# MRCS-8xDPDT-Relay.net
KiCad netlist of a schematic drawn in EAGLE
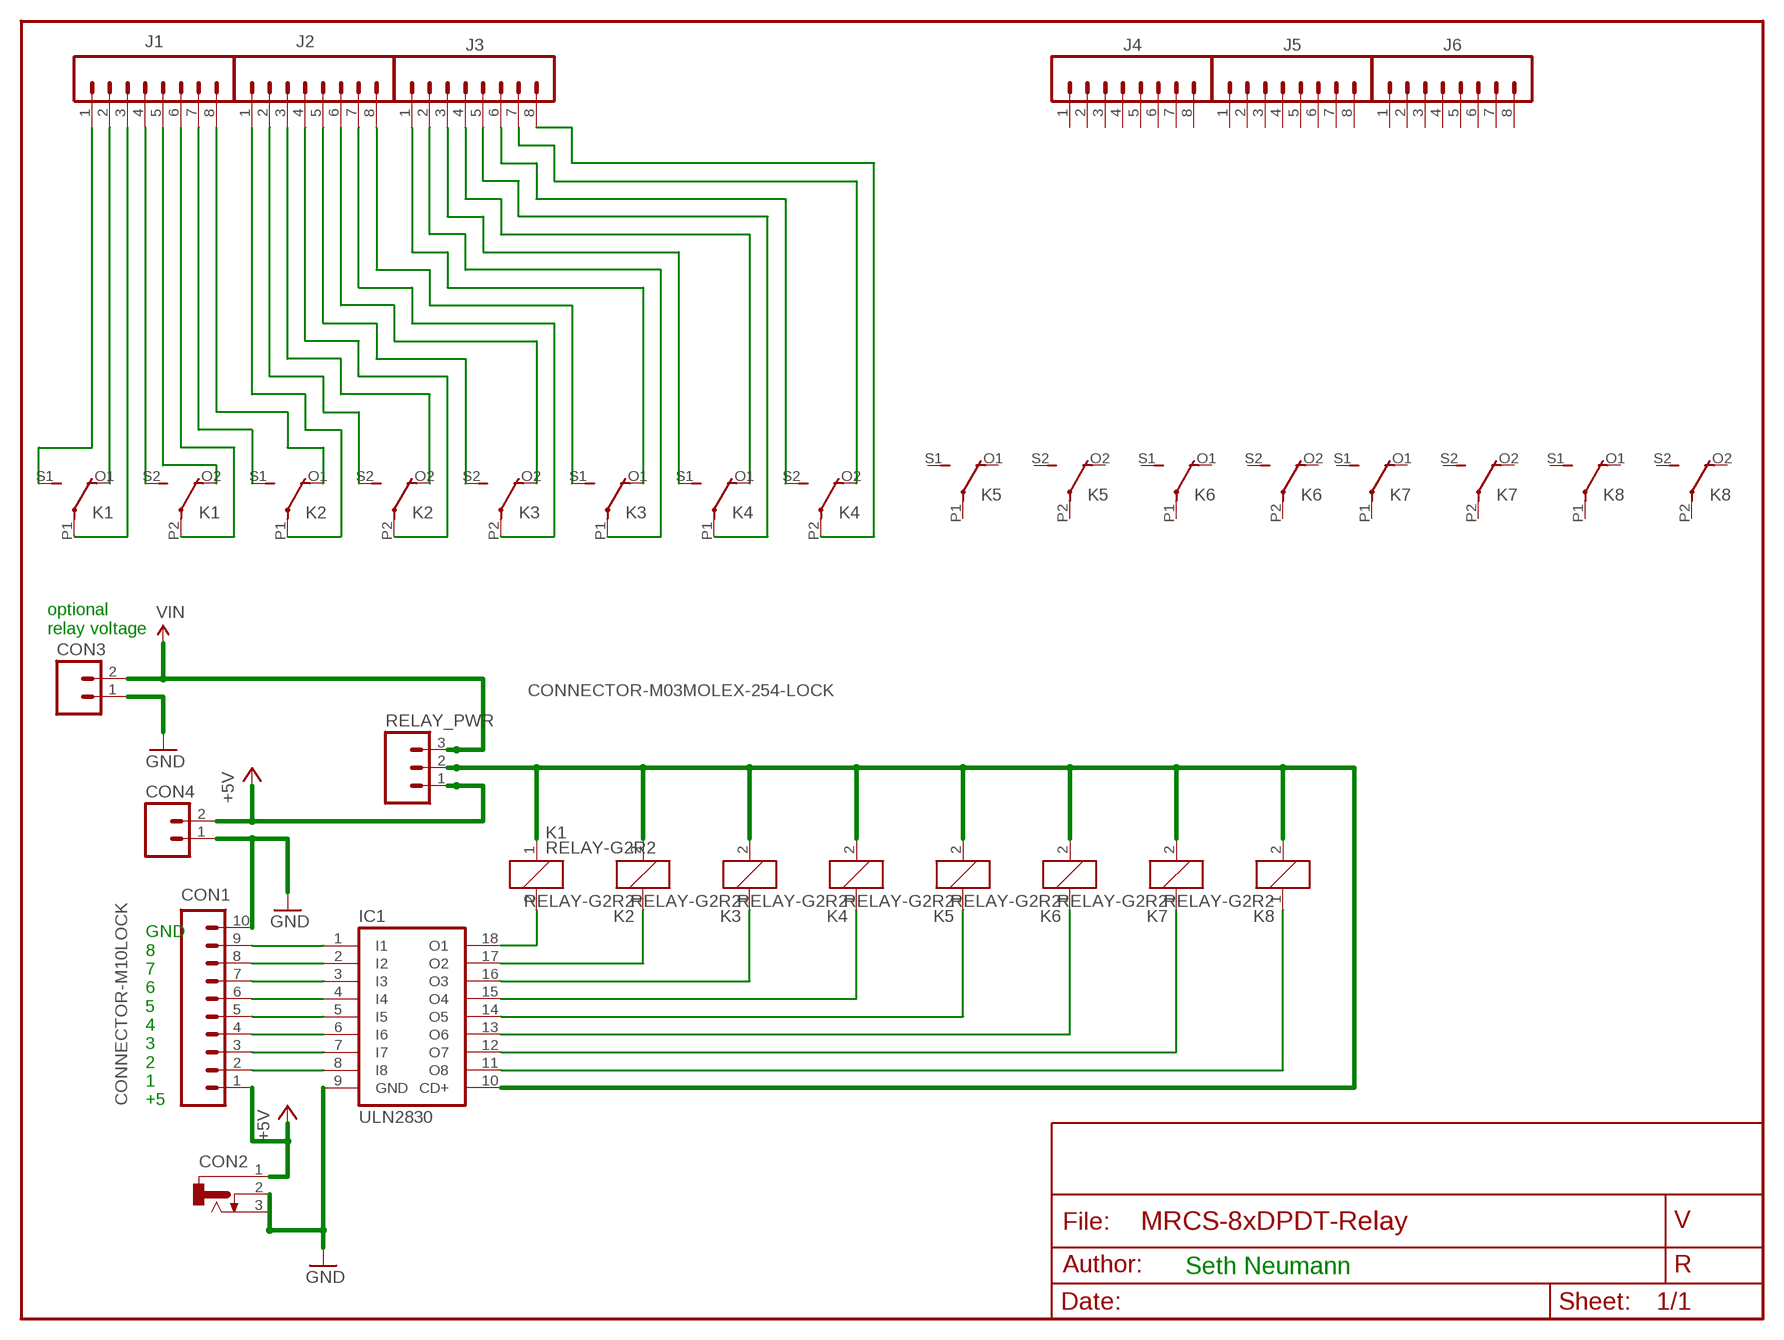
[diagram p0: schematic, sheet 1]

(export (version "E")
  (design (tool "Eeschema 10.0.6"))
  (components
    (comp (ref "CON1")
      (value "CONNECTOR-M10LOCK")
      (footprint "eagle-import:1X10_LOCK")
      (libsource (lib "eagle-import") (part "CONNECTOR-M10LOCK"))
    )
    (comp (ref "CON2")
      (value "CONNECTOR-DC-POWER-RA")
      (footprint "eagle-import:DCJ0202")
      (libsource (lib "eagle-import") (part "CONNECTOR-DC-POWER-RA"))
    )
    (comp (ref "CON3")
      (value "CONNECTOR-M023.5MM-LOCK")
      (footprint "eagle-import:SCREWTERMINAL-3.5MM-2_LOCK")
      (libsource (lib "eagle-import") (part "CONNECTOR-M023.5MM-LOCK"))
    )
    (comp (ref "CON4")
      (value "CONNECTOR-M023.5MM-LOCK")
      (footprint "eagle-import:SCREWTERMINAL-3.5MM-2_LOCK")
      (libsource (lib "eagle-import") (part "CONNECTOR-M023.5MM-LOCK"))
    )
    (comp (ref "IC1")
      (value "ULN2830")
      (footprint "eagle-import:DIL18")
      (libsource (lib "eagle-import") (part "ULN2803A"))
    )
    (comp (ref "J1")
      (value "CONNECTOR-M08LOCK")
      (footprint "eagle-import:1X08_LOCK")
      (libsource (lib "eagle-import") (part "CONNECTOR-M08LOCK"))
    )
    (comp (ref "J2")
      (value "CONNECTOR-M08LOCK")
      (footprint "eagle-import:1X08_LOCK")
      (libsource (lib "eagle-import") (part "CONNECTOR-M08LOCK"))
    )
    (comp (ref "J3")
      (value "CONNECTOR-M08LOCK")
      (footprint "eagle-import:1X08_LOCK")
      (libsource (lib "eagle-import") (part "CONNECTOR-M08LOCK"))
    )
    (comp (ref "J4")
      (value "CONNECTOR-M08LOCK")
      (footprint "eagle-import:1X08_LOCK")
      (libsource (lib "eagle-import") (part "CONNECTOR-M08LOCK"))
    )
    (comp (ref "J5")
      (value "CONNECTOR-M08LOCK")
      (footprint "eagle-import:1X08_LOCK")
      (libsource (lib "eagle-import") (part "CONNECTOR-M08LOCK"))
    )
    (comp (ref "J6")
      (value "CONNECTOR-M08LOCK")
      (footprint "eagle-import:1X08_LOCK")
      (libsource (lib "eagle-import") (part "CONNECTOR-M08LOCK"))
    )
    (comp (ref "K1")
      (value "RELAY-G2R2")
      (footprint "eagle-import:G2R2")
      (fields (field (name "MF") "OMRON COMPONENTS USA") (field (name "MPN") "G2R-2-DC6"))
      (libsource (lib "eagle-import") (part "RELAY-G2R2"))
    )
    (comp (ref "K2")
      (value "RELAY-G2R2")
      (footprint "eagle-import:G2R2")
      (fields (field (name "MF") "OMRON COMPONENTS USA") (field (name "MPN") "G2R-2-DC6"))
      (libsource (lib "eagle-import") (part "RELAY-G2R2"))
    )
    (comp (ref "K3")
      (value "RELAY-G2R2")
      (footprint "eagle-import:G2R2")
      (fields (field (name "MF") "OMRON COMPONENTS USA") (field (name "MPN") "G2R-2-DC6"))
      (libsource (lib "eagle-import") (part "RELAY-G2R2"))
    )
    (comp (ref "K4")
      (value "RELAY-G2R2")
      (footprint "eagle-import:G2R2")
      (fields (field (name "MF") "OMRON COMPONENTS USA") (field (name "MPN") "G2R-2-DC6"))
      (libsource (lib "eagle-import") (part "RELAY-G2R2"))
    )
    (comp (ref "K5")
      (value "RELAY-G2R2")
      (footprint "eagle-import:G2R2")
      (fields (field (name "MF") "OMRON COMPONENTS USA") (field (name "MPN") "G2R-2-DC6"))
      (libsource (lib "eagle-import") (part "RELAY-G2R2"))
    )
    (comp (ref "K6")
      (value "RELAY-G2R2")
      (footprint "eagle-import:G2R2")
      (fields (field (name "MF") "OMRON COMPONENTS USA") (field (name "MPN") "G2R-2-DC6"))
      (libsource (lib "eagle-import") (part "RELAY-G2R2"))
    )
    (comp (ref "K7")
      (value "RELAY-G2R2")
      (footprint "eagle-import:G2R2")
      (fields (field (name "MF") "OMRON COMPONENTS USA") (field (name "MPN") "G2R-2-DC6"))
      (libsource (lib "eagle-import") (part "RELAY-G2R2"))
    )
    (comp (ref "K8")
      (value "RELAY-G2R2")
      (footprint "eagle-import:G2R2")
      (fields (field (name "MF") "OMRON COMPONENTS USA") (field (name "MPN") "G2R-2-DC6"))
      (libsource (lib "eagle-import") (part "RELAY-G2R2"))
    )
    (comp (ref "RELAY_PWR")
      (value "CONNECTOR-M03MOLEX-254-LOCK")
      (footprint "eagle-import:MOLEX-1X3_LOCK")
      (libsource (lib "eagle-import") (part "CONNECTOR-M03MOLEX-254-LOCK"))
    )
  )
  (nets
    (net (code "1") (name "+5V") (class "Default")
      (node (ref "CON1") (pin "1") (pinfunction "1_1") (pintype "passive"))
      (node (ref "CON2") (pin "1") (pinfunction "1_1") (pintype "passive"))
      (node (ref "CON4") (pin "2") (pinfunction "B_2") (pintype "passive"))
      (node (ref "RELAY_PWR") (pin "1") (pinfunction "1_1") (pintype "passive"))
    )
    (net (code "2") (name "GND") (class "Default")
      (node (ref "CON1") (pin "10") (pinfunction "10_10") (pintype "passive"))
      (node (ref "CON2") (pin "2") (pinfunction "2_2") (pintype "passive"))
      (node (ref "CON2") (pin "3") (pinfunction "3_3") (pintype "passive"))
      (node (ref "CON3") (pin "1") (pinfunction "A_1") (pintype "passive"))
      (node (ref "CON4") (pin "1") (pinfunction "A_1") (pintype "passive"))
      (node (ref "IC1") (pin "9") (pinfunction "GND_9") (pintype "power_in"))
    )
    (net (code "3") (name "Net-(IC1-CD+)") (class "Default")
      (node (ref "IC1") (pin "10") (pinfunction "CD+_10") (pintype "passive"))
      (node (ref "K1") (pin "1") (pinfunction "1_1") (pintype "passive"))
      (node (ref "K2") (pin "2") (pinfunction "2_2") (pintype "passive"))
      (node (ref "K3") (pin "2") (pinfunction "2_2") (pintype "passive"))
      (node (ref "K4") (pin "2") (pinfunction "2_2") (pintype "passive"))
      (node (ref "K5") (pin "2") (pinfunction "2_2") (pintype "passive"))
      (node (ref "K6") (pin "2") (pinfunction "2_2") (pintype "passive"))
      (node (ref "K7") (pin "2") (pinfunction "2_2") (pintype "passive"))
      (node (ref "K8") (pin "2") (pinfunction "2_2") (pintype "passive"))
      (node (ref "RELAY_PWR") (pin "2") (pinfunction "2_2") (pintype "passive"))
    )
    (net (code "4") (name "Net-(IC1-I1)") (class "Default")
      (node (ref "CON1") (pin "9") (pinfunction "9_9") (pintype "passive"))
      (node (ref "IC1") (pin "1") (pinfunction "I1_1") (pintype "input"))
    )
    (net (code "5") (name "Net-(IC1-I2)") (class "Default")
      (node (ref "CON1") (pin "8") (pinfunction "8_8") (pintype "passive"))
      (node (ref "IC1") (pin "2") (pinfunction "I2_2") (pintype "input"))
    )
    (net (code "6") (name "Net-(IC1-I3)") (class "Default")
      (node (ref "CON1") (pin "7") (pinfunction "7_7") (pintype "passive"))
      (node (ref "IC1") (pin "3") (pinfunction "I3_3") (pintype "input"))
    )
    (net (code "7") (name "Net-(IC1-I4)") (class "Default")
      (node (ref "CON1") (pin "6") (pinfunction "6_6") (pintype "passive"))
      (node (ref "IC1") (pin "4") (pinfunction "I4_4") (pintype "input"))
    )
    (net (code "8") (name "Net-(IC1-I5)") (class "Default")
      (node (ref "CON1") (pin "5") (pinfunction "5_5") (pintype "passive"))
      (node (ref "IC1") (pin "5") (pinfunction "I5_5") (pintype "input"))
    )
    (net (code "9") (name "Net-(IC1-I6)") (class "Default")
      (node (ref "CON1") (pin "4") (pinfunction "4_4") (pintype "passive"))
      (node (ref "IC1") (pin "6") (pinfunction "I6_6") (pintype "input"))
    )
    (net (code "10") (name "Net-(IC1-I7)") (class "Default")
      (node (ref "CON1") (pin "3") (pinfunction "3_3") (pintype "passive"))
      (node (ref "IC1") (pin "7") (pinfunction "I7_7") (pintype "input"))
    )
    (net (code "11") (name "Net-(IC1-I8)") (class "Default")
      (node (ref "CON1") (pin "2") (pinfunction "2_2") (pintype "passive"))
      (node (ref "IC1") (pin "8") (pinfunction "I8_8") (pintype "input"))
    )
    (net (code "12") (name "Net-(IC1-O1)") (class "Default")
      (node (ref "IC1") (pin "18") (pinfunction "O1_18") (pintype "open_collector"))
      (node (ref "K1") (pin "2") (pinfunction "2_2") (pintype "passive"))
    )
    (net (code "13") (name "Net-(IC1-O2)") (class "Default")
      (node (ref "IC1") (pin "17") (pinfunction "O2_17") (pintype "open_collector"))
      (node (ref "K2") (pin "1") (pinfunction "1_1") (pintype "passive"))
    )
    (net (code "14") (name "Net-(IC1-O3)") (class "Default")
      (node (ref "IC1") (pin "16") (pinfunction "O3_16") (pintype "open_collector"))
      (node (ref "K3") (pin "1") (pinfunction "1_1") (pintype "passive"))
    )
    (net (code "15") (name "Net-(IC1-O4)") (class "Default")
      (node (ref "IC1") (pin "15") (pinfunction "O4_15") (pintype "open_collector"))
      (node (ref "K4") (pin "1") (pinfunction "1_1") (pintype "passive"))
    )
    (net (code "16") (name "Net-(IC1-O5)") (class "Default")
      (node (ref "IC1") (pin "14") (pinfunction "O5_14") (pintype "open_collector"))
      (node (ref "K5") (pin "1") (pinfunction "1_1") (pintype "passive"))
    )
    (net (code "17") (name "Net-(IC1-O6)") (class "Default")
      (node (ref "IC1") (pin "13") (pinfunction "O6_13") (pintype "open_collector"))
      (node (ref "K6") (pin "1") (pinfunction "1_1") (pintype "passive"))
    )
    (net (code "18") (name "Net-(IC1-O7)") (class "Default")
      (node (ref "IC1") (pin "12") (pinfunction "O7_12") (pintype "open_collector"))
      (node (ref "K7") (pin "1") (pinfunction "1_1") (pintype "passive"))
    )
    (net (code "19") (name "Net-(IC1-O8)") (class "Default")
      (node (ref "IC1") (pin "11") (pinfunction "O8_11") (pintype "open_collector"))
      (node (ref "K8") (pin "1") (pinfunction "1_1") (pintype "passive"))
    )
    (net (code "20") (name "Net-(K1B-O)") (class "Default")
      (node (ref "J1") (pin "2") (pinfunction "2_2") (pintype "passive"))
      (node (ref "K1") (pin "O1") (pinfunction "O_O1") (pintype "passive"))
    )
    (net (code "21") (name "Net-(K1B-P)") (class "Default")
      (node (ref "J1") (pin "3") (pinfunction "3_3") (pintype "passive"))
      (node (ref "K1") (pin "P1") (pinfunction "P_P1") (pintype "passive"))
    )
    (net (code "22") (name "Net-(K1B-S)") (class "Default")
      (node (ref "J1") (pin "1") (pinfunction "1_1") (pintype "passive"))
      (node (ref "K1") (pin "S1") (pinfunction "S_S1") (pintype "passive"))
    )
    (net (code "23") (name "Net-(K1C-O)") (class "Default")
      (node (ref "J1") (pin "5") (pinfunction "5_5") (pintype "passive"))
      (node (ref "K1") (pin "O2") (pinfunction "O_O2") (pintype "passive"))
    )
    (net (code "24") (name "Net-(K1C-P)") (class "Default")
      (node (ref "J1") (pin "6") (pinfunction "6_6") (pintype "passive"))
      (node (ref "K1") (pin "P2") (pinfunction "P_P2") (pintype "passive"))
    )
    (net (code "25") (name "Net-(K1C-S)") (class "Default")
      (node (ref "J1") (pin "4") (pinfunction "4_4") (pintype "passive"))
      (node (ref "K1") (pin "S2") (pinfunction "S_S2") (pintype "passive"))
    )
    (net (code "26") (name "Net-(K2B-O)") (class "Default")
      (node (ref "J1") (pin "8") (pinfunction "8_8") (pintype "passive"))
      (node (ref "K2") (pin "O1") (pinfunction "O_O1") (pintype "passive"))
    )
    (net (code "27") (name "Net-(K2B-P)") (class "Default")
      (node (ref "J2") (pin "1") (pinfunction "1_1") (pintype "passive"))
      (node (ref "K2") (pin "P1") (pinfunction "P_P1") (pintype "passive"))
    )
    (net (code "28") (name "Net-(K2B-S)") (class "Default")
      (node (ref "J1") (pin "7") (pinfunction "7_7") (pintype "passive"))
      (node (ref "K2") (pin "S1") (pinfunction "S_S1") (pintype "passive"))
    )
    (net (code "29") (name "Net-(K2C-O)") (class "Default")
      (node (ref "J2") (pin "3") (pinfunction "3_3") (pintype "passive"))
      (node (ref "K2") (pin "O2") (pinfunction "O_O2") (pintype "passive"))
    )
    (net (code "30") (name "Net-(K2C-P)") (class "Default")
      (node (ref "J2") (pin "4") (pinfunction "4_4") (pintype "passive"))
      (node (ref "K2") (pin "P2") (pinfunction "P_P2") (pintype "passive"))
    )
    (net (code "31") (name "Net-(K2C-S)") (class "Default")
      (node (ref "J2") (pin "2") (pinfunction "2_2") (pintype "passive"))
      (node (ref "K2") (pin "S2") (pinfunction "S_S2") (pintype "passive"))
    )
    (net (code "32") (name "Net-(K3B-O)") (class "Default")
      (node (ref "J3") (pin "1") (pinfunction "1_1") (pintype "passive"))
      (node (ref "K3") (pin "O1") (pinfunction "O_O1") (pintype "passive"))
    )
    (net (code "33") (name "Net-(K3B-P)") (class "Default")
      (node (ref "J3") (pin "2") (pinfunction "2_2") (pintype "passive"))
      (node (ref "K3") (pin "P1") (pinfunction "P_P1") (pintype "passive"))
    )
    (net (code "34") (name "Net-(K3B-S)") (class "Default")
      (node (ref "J2") (pin "8") (pinfunction "8_8") (pintype "passive"))
      (node (ref "K3") (pin "S1") (pinfunction "S_S1") (pintype "passive"))
    )
    (net (code "35") (name "Net-(K3C-O)") (class "Default")
      (node (ref "J2") (pin "6") (pinfunction "6_6") (pintype "passive"))
      (node (ref "K3") (pin "O2") (pinfunction "O_O2") (pintype "passive"))
    )
    (net (code "36") (name "Net-(K3C-P)") (class "Default")
      (node (ref "J2") (pin "7") (pinfunction "7_7") (pintype "passive"))
      (node (ref "K3") (pin "P2") (pinfunction "P_P2") (pintype "passive"))
    )
    (net (code "37") (name "Net-(K3C-S)") (class "Default")
      (node (ref "J2") (pin "5") (pinfunction "5_5") (pintype "passive"))
      (node (ref "K3") (pin "S2") (pinfunction "S_S2") (pintype "passive"))
    )
    (net (code "38") (name "Net-(K4B-O)") (class "Default")
      (node (ref "J3") (pin "4") (pinfunction "4_4") (pintype "passive"))
      (node (ref "K4") (pin "O1") (pinfunction "O_O1") (pintype "passive"))
    )
    (net (code "39") (name "Net-(K4B-P)") (class "Default")
      (node (ref "J3") (pin "5") (pinfunction "5_5") (pintype "passive"))
      (node (ref "K4") (pin "P1") (pinfunction "P_P1") (pintype "passive"))
    )
    (net (code "40") (name "Net-(K4B-S)") (class "Default")
      (node (ref "J3") (pin "3") (pinfunction "3_3") (pintype "passive"))
      (node (ref "K4") (pin "S1") (pinfunction "S_S1") (pintype "passive"))
    )
    (net (code "41") (name "Net-(K4C-O)") (class "Default")
      (node (ref "J3") (pin "7") (pinfunction "7_7") (pintype "passive"))
      (node (ref "K4") (pin "O2") (pinfunction "O_O2") (pintype "passive"))
    )
    (net (code "42") (name "Net-(K4C-P)") (class "Default")
      (node (ref "J3") (pin "8") (pinfunction "8_8") (pintype "passive"))
      (node (ref "K4") (pin "P2") (pinfunction "P_P2") (pintype "passive"))
    )
    (net (code "43") (name "Net-(K4C-S)") (class "Default")
      (node (ref "J3") (pin "6") (pinfunction "6_6") (pintype "passive"))
      (node (ref "K4") (pin "S2") (pinfunction "S_S2") (pintype "passive"))
    )
    (net (code "44") (name "VIN") (class "Default")
      (node (ref "CON3") (pin "2") (pinfunction "B_2") (pintype "passive"))
      (node (ref "RELAY_PWR") (pin "3") (pinfunction "3_3") (pintype "passive"))
    )
    (net (code "45") (name "unconnected-(J4-Pad1)") (class "Default")
      (node (ref "J4") (pin "1") (pinfunction "1_1") (pintype "passive"))
    )
    (net (code "46") (name "unconnected-(J4-Pad2)") (class "Default")
      (node (ref "J4") (pin "2") (pinfunction "2_2") (pintype "passive"))
    )
    (net (code "47") (name "unconnected-(J4-Pad3)") (class "Default")
      (node (ref "J4") (pin "3") (pinfunction "3_3") (pintype "passive"))
    )
    (net (code "48") (name "unconnected-(J4-Pad4)") (class "Default")
      (node (ref "J4") (pin "4") (pinfunction "4_4") (pintype "passive"))
    )
    (net (code "49") (name "unconnected-(J4-Pad5)") (class "Default")
      (node (ref "J4") (pin "5") (pinfunction "5_5") (pintype "passive"))
    )
    (net (code "50") (name "unconnected-(J4-Pad6)") (class "Default")
      (node (ref "J4") (pin "6") (pinfunction "6_6") (pintype "passive"))
    )
    (net (code "51") (name "unconnected-(J4-Pad7)") (class "Default")
      (node (ref "J4") (pin "7") (pinfunction "7_7") (pintype "passive"))
    )
    (net (code "52") (name "unconnected-(J4-Pad8)") (class "Default")
      (node (ref "J4") (pin "8") (pinfunction "8_8") (pintype "passive"))
    )
    (net (code "53") (name "unconnected-(J5-Pad1)") (class "Default")
      (node (ref "J5") (pin "1") (pinfunction "1_1") (pintype "passive"))
    )
    (net (code "54") (name "unconnected-(J5-Pad2)") (class "Default")
      (node (ref "J5") (pin "2") (pinfunction "2_2") (pintype "passive"))
    )
    (net (code "55") (name "unconnected-(J5-Pad3)") (class "Default")
      (node (ref "J5") (pin "3") (pinfunction "3_3") (pintype "passive"))
    )
    (net (code "56") (name "unconnected-(J5-Pad4)") (class "Default")
      (node (ref "J5") (pin "4") (pinfunction "4_4") (pintype "passive"))
    )
    (net (code "57") (name "unconnected-(J5-Pad5)") (class "Default")
      (node (ref "J5") (pin "5") (pinfunction "5_5") (pintype "passive"))
    )
    (net (code "58") (name "unconnected-(J5-Pad6)") (class "Default")
      (node (ref "J5") (pin "6") (pinfunction "6_6") (pintype "passive"))
    )
    (net (code "59") (name "unconnected-(J5-Pad7)") (class "Default")
      (node (ref "J5") (pin "7") (pinfunction "7_7") (pintype "passive"))
    )
    (net (code "60") (name "unconnected-(J5-Pad8)") (class "Default")
      (node (ref "J5") (pin "8") (pinfunction "8_8") (pintype "passive"))
    )
    (net (code "61") (name "unconnected-(J6-Pad1)") (class "Default")
      (node (ref "J6") (pin "1") (pinfunction "1_1") (pintype "passive"))
    )
    (net (code "62") (name "unconnected-(J6-Pad2)") (class "Default")
      (node (ref "J6") (pin "2") (pinfunction "2_2") (pintype "passive"))
    )
    (net (code "63") (name "unconnected-(J6-Pad3)") (class "Default")
      (node (ref "J6") (pin "3") (pinfunction "3_3") (pintype "passive"))
    )
    (net (code "64") (name "unconnected-(J6-Pad4)") (class "Default")
      (node (ref "J6") (pin "4") (pinfunction "4_4") (pintype "passive"))
    )
    (net (code "65") (name "unconnected-(J6-Pad5)") (class "Default")
      (node (ref "J6") (pin "5") (pinfunction "5_5") (pintype "passive"))
    )
    (net (code "66") (name "unconnected-(J6-Pad6)") (class "Default")
      (node (ref "J6") (pin "6") (pinfunction "6_6") (pintype "passive"))
    )
    (net (code "67") (name "unconnected-(J6-Pad7)") (class "Default")
      (node (ref "J6") (pin "7") (pinfunction "7_7") (pintype "passive"))
    )
    (net (code "68") (name "unconnected-(J6-Pad8)") (class "Default")
      (node (ref "J6") (pin "8") (pinfunction "8_8") (pintype "passive"))
    )
    (net (code "69") (name "unconnected-(K5B-O-PadO1)") (class "Default")
      (node (ref "K5") (pin "O1") (pinfunction "O_O1") (pintype "passive"))
    )
    (net (code "70") (name "unconnected-(K5B-P-PadP1)") (class "Default")
      (node (ref "K5") (pin "P1") (pinfunction "P_P1") (pintype "passive"))
    )
    (net (code "71") (name "unconnected-(K5B-S-PadS1)") (class "Default")
      (node (ref "K5") (pin "S1") (pinfunction "S_S1") (pintype "passive"))
    )
    (net (code "72") (name "unconnected-(K5C-O-PadO2)") (class "Default")
      (node (ref "K5") (pin "O2") (pinfunction "O_O2") (pintype "passive"))
    )
    (net (code "73") (name "unconnected-(K5C-P-PadP2)") (class "Default")
      (node (ref "K5") (pin "P2") (pinfunction "P_P2") (pintype "passive"))
    )
    (net (code "74") (name "unconnected-(K5C-S-PadS2)") (class "Default")
      (node (ref "K5") (pin "S2") (pinfunction "S_S2") (pintype "passive"))
    )
    (net (code "75") (name "unconnected-(K6B-O-PadO1)") (class "Default")
      (node (ref "K6") (pin "O1") (pinfunction "O_O1") (pintype "passive"))
    )
    (net (code "76") (name "unconnected-(K6B-P-PadP1)") (class "Default")
      (node (ref "K6") (pin "P1") (pinfunction "P_P1") (pintype "passive"))
    )
    (net (code "77") (name "unconnected-(K6B-S-PadS1)") (class "Default")
      (node (ref "K6") (pin "S1") (pinfunction "S_S1") (pintype "passive"))
    )
    (net (code "78") (name "unconnected-(K6C-O-PadO2)") (class "Default")
      (node (ref "K6") (pin "O2") (pinfunction "O_O2") (pintype "passive"))
    )
    (net (code "79") (name "unconnected-(K6C-P-PadP2)") (class "Default")
      (node (ref "K6") (pin "P2") (pinfunction "P_P2") (pintype "passive"))
    )
    (net (code "80") (name "unconnected-(K6C-S-PadS2)") (class "Default")
      (node (ref "K6") (pin "S2") (pinfunction "S_S2") (pintype "passive"))
    )
    (net (code "81") (name "unconnected-(K7B-O-PadO1)") (class "Default")
      (node (ref "K7") (pin "O1") (pinfunction "O_O1") (pintype "passive"))
    )
    (net (code "82") (name "unconnected-(K7B-P-PadP1)") (class "Default")
      (node (ref "K7") (pin "P1") (pinfunction "P_P1") (pintype "passive"))
    )
    (net (code "83") (name "unconnected-(K7B-S-PadS1)") (class "Default")
      (node (ref "K7") (pin "S1") (pinfunction "S_S1") (pintype "passive"))
    )
    (net (code "84") (name "unconnected-(K7C-O-PadO2)") (class "Default")
      (node (ref "K7") (pin "O2") (pinfunction "O_O2") (pintype "passive"))
    )
    (net (code "85") (name "unconnected-(K7C-P-PadP2)") (class "Default")
      (node (ref "K7") (pin "P2") (pinfunction "P_P2") (pintype "passive"))
    )
    (net (code "86") (name "unconnected-(K7C-S-PadS2)") (class "Default")
      (node (ref "K7") (pin "S2") (pinfunction "S_S2") (pintype "passive"))
    )
    (net (code "87") (name "unconnected-(K8B-O-PadO1)") (class "Default")
      (node (ref "K8") (pin "O1") (pinfunction "O_O1") (pintype "passive"))
    )
    (net (code "88") (name "unconnected-(K8B-P-PadP1)") (class "Default")
      (node (ref "K8") (pin "P1") (pinfunction "P_P1") (pintype "passive"))
    )
    (net (code "89") (name "unconnected-(K8B-S-PadS1)") (class "Default")
      (node (ref "K8") (pin "S1") (pinfunction "S_S1") (pintype "passive"))
    )
    (net (code "90") (name "unconnected-(K8C-O-PadO2)") (class "Default")
      (node (ref "K8") (pin "O2") (pinfunction "O_O2") (pintype "passive"))
    )
    (net (code "91") (name "unconnected-(K8C-P-PadP2)") (class "Default")
      (node (ref "K8") (pin "P2") (pinfunction "P_P2") (pintype "passive"))
    )
    (net (code "92") (name "unconnected-(K8C-S-PadS2)") (class "Default")
      (node (ref "K8") (pin "S2") (pinfunction "S_S2") (pintype "passive"))
    )
  )
)
